# mos_motor.net
KiCad netlist of a schematic drawn in Altium Designer
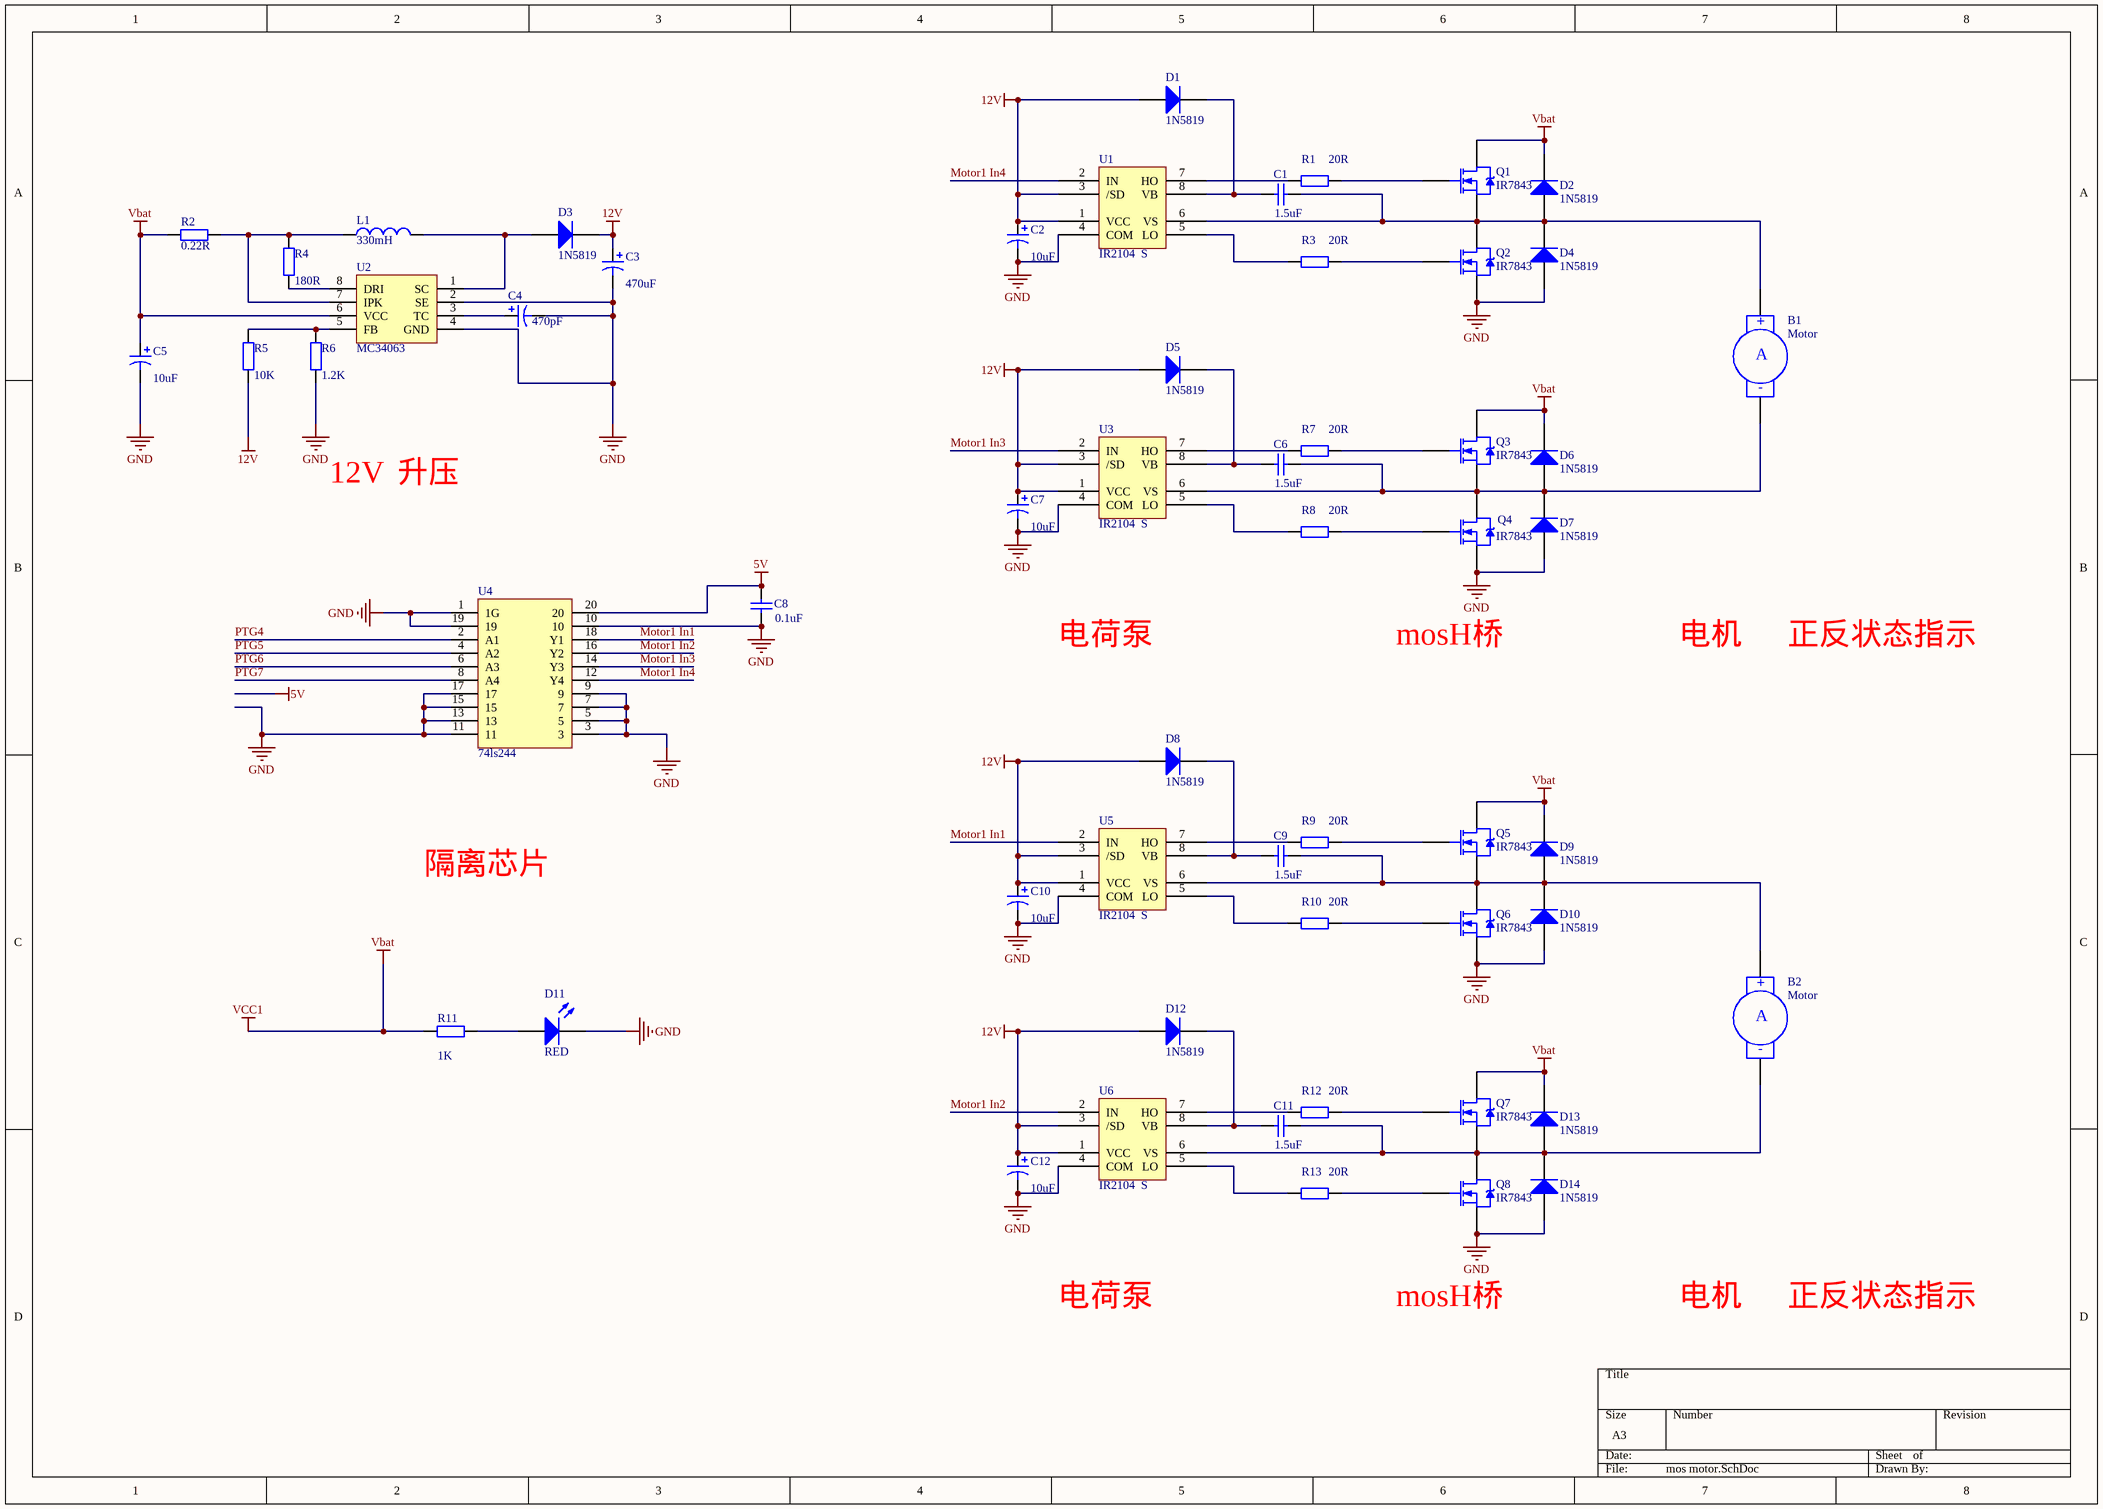
[diagram p0: mos motor.SchDoc]

(export (version "E")
  (design (tool "Eeschema 10.0.6"))
  (components
    (comp (ref "B1")
      (value "Motor")
      (footprint "KF301-2P")
      (description "Servo Motor")
      (fields (field (name "PUBLISHER") "Altium Limited"))
      (libsource (lib "Miscellaneous Devices") (part "Motor Servo"))
    )
    (comp (ref "B2")
      (value "Motor")
      (footprint "KF301-2P")
      (description "Servo Motor")
      (fields (field (name "PUBLISHER") "Altium Limited"))
      (libsource (lib "Miscellaneous Devices") (part "Motor Servo"))
    )
    (comp (ref "C1")
      (value "1.5uF")
      (footprint "0805(2012)")
      (description "Capacitor")
      (fields (field (name "Comment") "Cap") (field (name "PUBLISHER") "Altium Limited"))
      (libsource (lib "Miscellaneous Devices") (part "Cap"))
    )
    (comp (ref "C2")
      (value "10uF")
      (footprint "SOD-323(0805)")
      (description "Polarized Capacitor (Radial)")
      (fields (field (name "Comment") "Cap Pol1") (field (name "PUBLISHER") "Altium Limited"))
      (libsource (lib "Miscellaneous Devices") (part "Cap Pol1"))
    )
    (comp (ref "C3")
      (value "470uF")
      (footprint "RB5-10.5")
      (description "Polarized Capacitor (Radial)")
      (fields (field (name "Comment") "Cap Pol1") (field (name "PUBLISHER") "Altium Limited"))
      (libsource (lib "Miscellaneous Devices") (part "Cap Pol1"))
    )
    (comp (ref "C4")
      (value "470pF")
      (footprint "SOD-323(0805)")
      (description "Polarized Capacitor (Radial)")
      (fields (field (name "Comment") "Cap Pol1") (field (name "PUBLISHER") "Altium Limited"))
      (libsource (lib "Miscellaneous Devices") (part "Cap Pol1"))
    )
    (comp (ref "C5")
      (value "10uF")
      (footprint "SOD-323(0805)")
      (description "Polarized Capacitor (Radial)")
      (fields (field (name "Comment") "Cap Pol1") (field (name "PUBLISHER") "Altium Limited"))
      (libsource (lib "Miscellaneous Devices") (part "Cap Pol1"))
    )
    (comp (ref "C6")
      (value "1.5uF")
      (footprint "0805(2012)")
      (description "Capacitor")
      (fields (field (name "Comment") "Cap") (field (name "PUBLISHER") "Altium Limited"))
      (libsource (lib "Miscellaneous Devices") (part "Cap"))
    )
    (comp (ref "C7")
      (value "10uF")
      (footprint "SOD-323(0805)")
      (description "Polarized Capacitor (Radial)")
      (fields (field (name "Comment") "Cap Pol1") (field (name "PUBLISHER") "Altium Limited"))
      (libsource (lib "Miscellaneous Devices") (part "Cap Pol1"))
    )
    (comp (ref "C8")
      (value "0.1uF")
      (footprint "0805(2012)")
      (description "Capacitor")
      (fields (field (name "Comment") "Cap") (field (name "PUBLISHER") "Altium Limited"))
      (libsource (lib "Miscellaneous Devices") (part "Cap"))
    )
    (comp (ref "C9")
      (value "1.5uF")
      (footprint "0805(2012)")
      (description "Capacitor")
      (fields (field (name "Comment") "Cap") (field (name "PUBLISHER") "Altium Limited"))
      (libsource (lib "Miscellaneous Devices") (part "Cap"))
    )
    (comp (ref "C10")
      (value "10uF")
      (footprint "SOD-323(0805)")
      (description "Polarized Capacitor (Radial)")
      (fields (field (name "Comment") "Cap Pol1") (field (name "PUBLISHER") "Altium Limited"))
      (libsource (lib "Miscellaneous Devices") (part "Cap Pol1"))
    )
    (comp (ref "C11")
      (value "1.5uF")
      (footprint "0805(2012)")
      (description "Capacitor")
      (fields (field (name "Comment") "Cap") (field (name "PUBLISHER") "Altium Limited"))
      (libsource (lib "Miscellaneous Devices") (part "Cap"))
    )
    (comp (ref "C12")
      (value "10uF")
      (footprint "SOD-323(0805)")
      (description "Polarized Capacitor (Radial)")
      (fields (field (name "Comment") "Cap Pol1") (field (name "PUBLISHER") "Altium Limited"))
      (libsource (lib "Miscellaneous Devices") (part "Cap Pol1"))
    )
    (comp (ref "D1")
      (value "1N5819")
      (footprint "0805(2012)")
      (description "Silicon Epitaxial Planar Diode for Various Detector, Modulator, Demodulator")
      (fields (field (name "PUBLISHER") "Altium Limited"))
      (libsource (lib "Renesas Diode") (part "1N4148"))
    )
    (comp (ref "D2")
      (value "1N5819")
      (footprint "0805(2012)")
      (description "Silicon Epitaxial Planar Diode for Various Detector, Modulator, Demodulator")
      (fields (field (name "PUBLISHER") "Altium Limited"))
      (libsource (lib "Renesas Diode") (part "1N4148"))
    )
    (comp (ref "D3")
      (value "1N5819")
      (footprint "0805(2012)")
      (description "Silicon Epitaxial Planar Diode for Various Detector, Modulator, Demodulator")
      (fields (field (name "PUBLISHER") "Altium Limited"))
      (libsource (lib "Renesas Diode") (part "1N4148"))
    )
    (comp (ref "D4")
      (value "1N5819")
      (footprint "0805(2012)")
      (description "Silicon Epitaxial Planar Diode for Various Detector, Modulator, Demodulator")
      (fields (field (name "PUBLISHER") "Altium Limited"))
      (libsource (lib "13th_motor") (part "1N4148"))
    )
    (comp (ref "D5")
      (value "1N5819")
      (footprint "0805(2012)")
      (description "Silicon Epitaxial Planar Diode for Various Detector, Modulator, Demodulator")
      (fields (field (name "PUBLISHER") "Altium Limited"))
      (libsource (lib "Renesas Diode") (part "1N4148"))
    )
    (comp (ref "D6")
      (value "1N5819")
      (footprint "0805(2012)")
      (description "Silicon Epitaxial Planar Diode for Various Detector, Modulator, Demodulator")
      (fields (field (name "PUBLISHER") "Altium Limited"))
      (libsource (lib "Renesas Diode") (part "1N4148"))
    )
    (comp (ref "D7")
      (value "1N5819")
      (footprint "0805(2012)")
      (description "Silicon Epitaxial Planar Diode for Various Detector, Modulator, Demodulator")
      (fields (field (name "PUBLISHER") "Altium Limited"))
      (libsource (lib "Renesas Diode") (part "1N4148"))
    )
    (comp (ref "D8")
      (value "1N5819")
      (footprint "0805(2012)")
      (description "Silicon Epitaxial Planar Diode for Various Detector, Modulator, Demodulator")
      (fields (field (name "PUBLISHER") "Altium Limited"))
      (libsource (lib "Renesas Diode") (part "1N4148"))
    )
    (comp (ref "D9")
      (value "1N5819")
      (footprint "0805(2012)")
      (description "Silicon Epitaxial Planar Diode for Various Detector, Modulator, Demodulator")
      (fields (field (name "PUBLISHER") "Altium Limited"))
      (libsource (lib "Renesas Diode") (part "1N4148"))
    )
    (comp (ref "D10")
      (value "1N5819")
      (footprint "0805(2012)")
      (description "Silicon Epitaxial Planar Diode for Various Detector, Modulator, Demodulator")
      (fields (field (name "PUBLISHER") "Altium Limited"))
      (libsource (lib "Renesas Diode") (part "1N4148"))
    )
    (comp (ref "D11")
      (value "RED")
      (footprint "0805LED")
      (description "Typical RED, GREEN, YELLOW, AMBER GaAs LED")
      (fields (field (name "PUBLISHER") "Altium Limited"))
      (libsource (lib "Miscellaneous Devices") (part "LED2"))
    )
    (comp (ref "D12")
      (value "1N5819")
      (footprint "0805(2012)")
      (description "Silicon Epitaxial Planar Diode for Various Detector, Modulator, Demodulator")
      (fields (field (name "PUBLISHER") "Altium Limited"))
      (libsource (lib "Renesas Diode") (part "1N4148"))
    )
    (comp (ref "D13")
      (value "1N5819")
      (footprint "0805(2012)")
      (description "Silicon Epitaxial Planar Diode for Various Detector, Modulator, Demodulator")
      (fields (field (name "PUBLISHER") "Altium Limited"))
      (libsource (lib "Renesas Diode") (part "1N4148"))
    )
    (comp (ref "D14")
      (value "1N5819")
      (footprint "0805(2012)")
      (description "Silicon Epitaxial Planar Diode for Various Detector, Modulator, Demodulator")
      (fields (field (name "PUBLISHER") "Altium Limited"))
      (libsource (lib "Renesas Diode") (part "1N4148"))
    )
    (comp (ref "L1")
      (value "330mH")
      (footprint "电感10*12")
      (description "Inductor")
      (fields (field (name "PUBLISHER") "Altium Limited"))
      (libsource (lib "Miscellaneous Devices") (part "Inductor"))
    )
    (comp (ref "Q1")
      (value "IR7843")
      (footprint "LR7843")
      (description "N-Channel Power MOSFET")
      (fields (field (name "PUBLISHER") "Altium Limited"))
      (libsource (lib "PowerIn") (part "IR7843"))
    )
    (comp (ref "Q2")
      (value "IR7843")
      (footprint "LR7843")
      (description "N-Channel Power MOSFET")
      (fields (field (name "PUBLISHER") "Altium Limited"))
      (libsource (lib "PowerIn") (part "IR7843"))
    )
    (comp (ref "Q3")
      (value "IR7843")
      (footprint "LR7843")
      (description "N-Channel Power MOSFET")
      (fields (field (name "PUBLISHER") "Altium Limited"))
      (libsource (lib "PowerIn") (part "IR7843"))
    )
    (comp (ref "Q4")
      (value "IR7843")
      (footprint "LR7843")
      (description "N-Channel Power MOSFET")
      (fields (field (name "PUBLISHER") "Altium Limited"))
      (libsource (lib "PowerIn") (part "IR7843"))
    )
    (comp (ref "Q5")
      (value "IR7843")
      (footprint "LR7843")
      (description "N-Channel Power MOSFET")
      (fields (field (name "PUBLISHER") "Altium Limited"))
      (libsource (lib "PowerIn") (part "IR7843"))
    )
    (comp (ref "Q6")
      (value "IR7843")
      (footprint "LR7843")
      (description "N-Channel Power MOSFET")
      (fields (field (name "PUBLISHER") "Altium Limited"))
      (libsource (lib "PowerIn") (part "IR7843"))
    )
    (comp (ref "Q7")
      (value "IR7843")
      (footprint "LR7843")
      (description "N-Channel Power MOSFET")
      (fields (field (name "PUBLISHER") "Altium Limited"))
      (libsource (lib "PowerIn") (part "IR7843"))
    )
    (comp (ref "Q8")
      (value "IR7843")
      (footprint "LR7843")
      (description "N-Channel Power MOSFET")
      (fields (field (name "PUBLISHER") "Altium Limited"))
      (libsource (lib "PowerIn") (part "IR7843"))
    )
    (comp (ref "R1")
      (value "20R")
      (footprint "0805(2012)")
      (description "Resistor")
      (fields (field (name "Comment") "Res2") (field (name "PUBLISHER") "Altium Limited"))
      (libsource (lib "altium-import") (part "root_0_Res2_"))
    )
    (comp (ref "R2")
      (value "0.22R")
      (footprint "1206(3216)")
      (description "Resistor")
      (fields (field (name "Comment") "Res2") (field (name "PUBLISHER") "Altium Limited"))
      (libsource (lib "altium-import") (part "root_2_Res2_"))
    )
    (comp (ref "R3")
      (value "20R")
      (footprint "0805(2012)")
      (description "Resistor")
      (fields (field (name "Comment") "Res2") (field (name "PUBLISHER") "Altium Limited"))
      (libsource (lib "altium-import") (part "root_0_Res2_"))
    )
    (comp (ref "R4")
      (value "180R")
      (footprint "0805(2012)")
      (description "Resistor")
      (fields (field (name "Comment") "Res2") (field (name "PUBLISHER") "Altium Limited"))
      (libsource (lib "altium-import") (part "root_1_Res2_"))
    )
    (comp (ref "R5")
      (value "10K")
      (footprint "0805(2012)")
      (description "Resistor")
      (fields (field (name "Comment") "Res2") (field (name "PUBLISHER") "Altium Limited"))
      (libsource (lib "altium-import") (part "root_1_Res2_"))
    )
    (comp (ref "R6")
      (value "1.2K")
      (footprint "0805(2012)")
      (description "Resistor")
      (fields (field (name "Comment") "Res2") (field (name "PUBLISHER") "Altium Limited"))
      (libsource (lib "altium-import") (part "root_1_Res2_"))
    )
    (comp (ref "R7")
      (value "20R")
      (footprint "0805(2012)")
      (description "Resistor")
      (fields (field (name "Comment") "Res2") (field (name "PUBLISHER") "Altium Limited"))
      (libsource (lib "altium-import") (part "root_0_Res2_"))
    )
    (comp (ref "R8")
      (value "20R")
      (footprint "0805(2012)")
      (description "Resistor")
      (fields (field (name "Comment") "Res2") (field (name "PUBLISHER") "Altium Limited"))
      (libsource (lib "altium-import") (part "root_0_Res2_"))
    )
    (comp (ref "R9")
      (value "20R")
      (footprint "0805(2012)")
      (description "Resistor")
      (fields (field (name "Comment") "Res2") (field (name "PUBLISHER") "Altium Limited"))
      (libsource (lib "altium-import") (part "root_0_Res2_"))
    )
    (comp (ref "R10")
      (value "20R")
      (footprint "0805(2012)")
      (description "Resistor")
      (fields (field (name "Comment") "Res2") (field (name "PUBLISHER") "Altium Limited"))
      (libsource (lib "altium-import") (part "root_0_Res2_"))
    )
    (comp (ref "R11")
      (value "1K")
      (footprint "0805(2012)")
      (description "Resistor")
      (fields (field (name "Comment") "Res2") (field (name "PUBLISHER") "Altium Limited"))
      (libsource (lib "Miscellaneous Devices") (part "Res2"))
    )
    (comp (ref "R12")
      (value "20R")
      (footprint "0805(2012)")
      (description "Resistor")
      (fields (field (name "Comment") "Res2") (field (name "PUBLISHER") "Altium Limited"))
      (libsource (lib "altium-import") (part "root_0_Res2_"))
    )
    (comp (ref "R13")
      (value "20R")
      (footprint "0805(2012)")
      (description "Resistor")
      (fields (field (name "Comment") "Res2") (field (name "PUBLISHER") "Altium Limited"))
      (libsource (lib "altium-import") (part "root_0_Res2_"))
    )
    (comp (ref "U1") (value "IR2104  S") (footprint "IR2104S") (libsource (lib "IR2104S") (part "IR2104  S")))
    (comp (ref "U2") (value "MC34063") (footprint "MC34063") (libsource (lib "MC34063") (part "Component_1")))
    (comp (ref "U3") (value "IR2104  S") (footprint "IR2104S") (libsource (lib "IR2104S") (part "IR2104  S")))
    (comp (ref "U4") (value "74ls244") (footprint "74ls244Da") (libsource (lib "MOS motor") (part "74ls244")))
    (comp (ref "U5") (value "IR2104  S") (footprint "IR2104S") (libsource (lib "IR2104S") (part "IR2104  S")))
    (comp (ref "U6") (value "IR2104  S") (footprint "IR2104S") (libsource (lib "IR2104S") (part "IR2104  S")))
  )
  (nets
    (net (code "1") (name "/Motor1 In1") (class "Default")
      (node (ref "U4") (pin "18") (pinfunction "Y1_18") (pintype "passive"))
      (node (ref "U5") (pin "2") (pinfunction "IN_2") (pintype "passive"))
    )
    (net (code "2") (name "/Motor1 In2") (class "Default")
      (node (ref "U4") (pin "16") (pinfunction "Y2_16") (pintype "passive"))
      (node (ref "U6") (pin "2") (pinfunction "IN_2") (pintype "passive"))
    )
    (net (code "3") (name "/Motor1 In3") (class "Default")
      (node (ref "U3") (pin "2") (pinfunction "IN_2") (pintype "passive"))
      (node (ref "U4") (pin "14") (pinfunction "Y3_14") (pintype "passive"))
    )
    (net (code "4") (name "/Motor1 In4") (class "Default")
      (node (ref "U1") (pin "2") (pinfunction "IN_2") (pintype "passive"))
      (node (ref "U4") (pin "12") (pinfunction "Y4_12") (pintype "passive"))
    )
    (net (code "5") (name "/PTG4") (class "Default")
      (node (ref "U4") (pin "2") (pinfunction "A1_2") (pintype "passive"))
    )
    (net (code "6") (name "/PTG5") (class "Default")
      (node (ref "U4") (pin "4") (pinfunction "A2_4") (pintype "passive"))
    )
    (net (code "7") (name "/PTG6") (class "Default")
      (node (ref "U4") (pin "6") (pinfunction "A3_6") (pintype "passive"))
    )
    (net (code "8") (name "/PTG7") (class "Default")
      (node (ref "U4") (pin "8") (pinfunction "A4_8") (pintype "passive"))
    )
    (net (code "9") (name "5V") (class "Default")
      (node (ref "C8") (pin "2") (pinfunction "2_2") (pintype "passive"))
      (node (ref "U4") (pin "20") (pinfunction "20_20") (pintype "passive"))
    )
    (net (code "10") (name "12V") (class "Default")
      (node (ref "C10") (pin "1") (pinfunction "1_1") (pintype "passive"))
      (node (ref "C12") (pin "1") (pinfunction "1_1") (pintype "passive"))
      (node (ref "C2") (pin "1") (pinfunction "1_1") (pintype "passive"))
      (node (ref "C3") (pin "1") (pinfunction "1_1") (pintype "passive"))
      (node (ref "C7") (pin "1") (pinfunction "1_1") (pintype "passive"))
      (node (ref "D1") (pin "2") (pinfunction "A_2") (pintype "passive"))
      (node (ref "D12") (pin "2") (pinfunction "A_2") (pintype "passive"))
      (node (ref "D3") (pin "1") (pinfunction "K_1") (pintype "passive"))
      (node (ref "D5") (pin "2") (pinfunction "A_2") (pintype "passive"))
      (node (ref "D8") (pin "2") (pinfunction "A_2") (pintype "passive"))
      (node (ref "R5") (pin "1") (pinfunction "1_1") (pintype "passive"))
      (node (ref "U1") (pin "1") (pinfunction "VCC_1") (pintype "passive"))
      (node (ref "U1") (pin "3") (pinfunction "/SD_3") (pintype "passive"))
      (node (ref "U3") (pin "1") (pinfunction "VCC_1") (pintype "passive"))
      (node (ref "U3") (pin "3") (pinfunction "/SD_3") (pintype "passive"))
      (node (ref "U5") (pin "1") (pinfunction "VCC_1") (pintype "passive"))
      (node (ref "U5") (pin "3") (pinfunction "/SD_3") (pintype "passive"))
      (node (ref "U6") (pin "1") (pinfunction "VCC_1") (pintype "passive"))
      (node (ref "U6") (pin "3") (pinfunction "/SD_3") (pintype "passive"))
    )
    (net (code "11") (name "GND") (class "Default")
      (node (ref "C10") (pin "2") (pinfunction "2_2") (pintype "passive"))
      (node (ref "C12") (pin "2") (pinfunction "2_2") (pintype "passive"))
      (node (ref "C2") (pin "2") (pinfunction "2_2") (pintype "passive"))
      (node (ref "C3") (pin "2") (pinfunction "2_2") (pintype "passive"))
      (node (ref "C4") (pin "2") (pinfunction "2_2") (pintype "passive"))
      (node (ref "C5") (pin "2") (pinfunction "2_2") (pintype "passive"))
      (node (ref "C7") (pin "2") (pinfunction "2_2") (pintype "passive"))
      (node (ref "C8") (pin "1") (pinfunction "1_1") (pintype "passive"))
      (node (ref "D10") (pin "2") (pinfunction "A_2") (pintype "passive"))
      (node (ref "D11") (pin "2") (pinfunction "K_2") (pintype "passive"))
      (node (ref "D14") (pin "2") (pinfunction "A_2") (pintype "passive"))
      (node (ref "D4") (pin "2") (pinfunction "A_2") (pintype "passive"))
      (node (ref "D7") (pin "2") (pinfunction "A_2") (pintype "passive"))
      (node (ref "Q2") (pin "3") (pinfunction "S_3") (pintype "passive"))
      (node (ref "Q4") (pin "3") (pinfunction "S_3") (pintype "passive"))
      (node (ref "Q6") (pin "3") (pinfunction "S_3") (pintype "passive"))
      (node (ref "Q8") (pin "3") (pinfunction "S_3") (pintype "passive"))
      (node (ref "R6") (pin "1") (pinfunction "1_1") (pintype "passive"))
      (node (ref "U1") (pin "4") (pinfunction "COM_4") (pintype "passive"))
      (node (ref "U2") (pin "2") (pinfunction "SE_2") (pintype "passive"))
      (node (ref "U2") (pin "4") (pinfunction "GND_4") (pintype "passive"))
      (node (ref "U3") (pin "4") (pinfunction "COM_4") (pintype "passive"))
      (node (ref "U4") (pin "1") (pinfunction "1G_1") (pintype "passive"))
      (node (ref "U4") (pin "10") (pinfunction "10_10") (pintype "passive"))
      (node (ref "U4") (pin "11") (pinfunction "11_11") (pintype "passive"))
      (node (ref "U4") (pin "13") (pinfunction "13_13") (pintype "passive"))
      (node (ref "U4") (pin "15") (pinfunction "15_15") (pintype "passive"))
      (node (ref "U4") (pin "17") (pinfunction "17_17") (pintype "passive"))
      (node (ref "U4") (pin "19") (pinfunction "19_19") (pintype "passive"))
      (node (ref "U4") (pin "3") (pinfunction "3_3") (pintype "passive"))
      (node (ref "U4") (pin "5") (pinfunction "5_5") (pintype "passive"))
      (node (ref "U4") (pin "7") (pinfunction "7_7") (pintype "passive"))
      (node (ref "U4") (pin "9") (pinfunction "9_9") (pintype "passive"))
      (node (ref "U5") (pin "4") (pinfunction "COM_4") (pintype "passive"))
      (node (ref "U6") (pin "4") (pinfunction "COM_4") (pintype "passive"))
    )
    (net (code "12") (name "Net-(B1-+)") (class "Default")
      (node (ref "B1") (pin "1") (pinfunction "+_1") (pintype "passive"))
      (node (ref "C1") (pin "2") (pinfunction "2_2") (pintype "passive"))
      (node (ref "D2") (pin "2") (pinfunction "A_2") (pintype "passive"))
      (node (ref "D4") (pin "1") (pinfunction "K_1") (pintype "passive"))
      (node (ref "Q1") (pin "3") (pinfunction "S_3") (pintype "passive"))
      (node (ref "Q2") (pin "2") (pinfunction "D_2") (pintype "passive"))
      (node (ref "U1") (pin "6") (pinfunction "VS_6") (pintype "passive"))
    )
    (net (code "13") (name "Net-(B1--)") (class "Default")
      (node (ref "B1") (pin "2") (pinfunction "-_2") (pintype "passive"))
      (node (ref "C6") (pin "2") (pinfunction "2_2") (pintype "passive"))
      (node (ref "D6") (pin "2") (pinfunction "A_2") (pintype "passive"))
      (node (ref "D7") (pin "1") (pinfunction "K_1") (pintype "passive"))
      (node (ref "Q3") (pin "3") (pinfunction "S_3") (pintype "passive"))
      (node (ref "Q4") (pin "2") (pinfunction "D_2") (pintype "passive"))
      (node (ref "U3") (pin "6") (pinfunction "VS_6") (pintype "passive"))
    )
    (net (code "14") (name "Net-(B2-+)") (class "Default")
      (node (ref "B2") (pin "1") (pinfunction "+_1") (pintype "passive"))
      (node (ref "C9") (pin "2") (pinfunction "2_2") (pintype "passive"))
      (node (ref "D10") (pin "1") (pinfunction "K_1") (pintype "passive"))
      (node (ref "D9") (pin "2") (pinfunction "A_2") (pintype "passive"))
      (node (ref "Q5") (pin "3") (pinfunction "S_3") (pintype "passive"))
      (node (ref "Q6") (pin "2") (pinfunction "D_2") (pintype "passive"))
      (node (ref "U5") (pin "6") (pinfunction "VS_6") (pintype "passive"))
    )
    (net (code "15") (name "Net-(B2--)") (class "Default")
      (node (ref "B2") (pin "2") (pinfunction "-_2") (pintype "passive"))
      (node (ref "C11") (pin "2") (pinfunction "2_2") (pintype "passive"))
      (node (ref "D13") (pin "2") (pinfunction "A_2") (pintype "passive"))
      (node (ref "D14") (pin "1") (pinfunction "K_1") (pintype "passive"))
      (node (ref "Q7") (pin "3") (pinfunction "S_3") (pintype "passive"))
      (node (ref "Q8") (pin "2") (pinfunction "D_2") (pintype "passive"))
      (node (ref "U6") (pin "6") (pinfunction "VS_6") (pintype "passive"))
    )
    (net (code "16") (name "Net-(D1-K)") (class "Default")
      (node (ref "C1") (pin "1") (pinfunction "1_1") (pintype "passive"))
      (node (ref "D1") (pin "1") (pinfunction "K_1") (pintype "passive"))
      (node (ref "U1") (pin "8") (pinfunction "VB_8") (pintype "passive"))
    )
    (net (code "17") (name "Net-(D3-A)") (class "Default")
      (node (ref "D3") (pin "2") (pinfunction "A_2") (pintype "passive"))
      (node (ref "L1") (pin "2") (pinfunction "2_2") (pintype "passive"))
      (node (ref "U2") (pin "1") (pinfunction "SC_1") (pintype "passive"))
    )
    (net (code "18") (name "Net-(D5-K)") (class "Default")
      (node (ref "C6") (pin "1") (pinfunction "1_1") (pintype "passive"))
      (node (ref "D5") (pin "1") (pinfunction "K_1") (pintype "passive"))
      (node (ref "U3") (pin "8") (pinfunction "VB_8") (pintype "passive"))
    )
    (net (code "19") (name "Net-(D8-K)") (class "Default")
      (node (ref "C9") (pin "1") (pinfunction "1_1") (pintype "passive"))
      (node (ref "D8") (pin "1") (pinfunction "K_1") (pintype "passive"))
      (node (ref "U5") (pin "8") (pinfunction "VB_8") (pintype "passive"))
    )
    (net (code "20") (name "Net-(D11-A)") (class "Default")
      (node (ref "D11") (pin "1") (pinfunction "A_1") (pintype "passive"))
      (node (ref "R11") (pin "2") (pinfunction "2_2") (pintype "passive"))
    )
    (net (code "21") (name "Net-(D12-K)") (class "Default")
      (node (ref "C11") (pin "1") (pinfunction "1_1") (pintype "passive"))
      (node (ref "D12") (pin "1") (pinfunction "K_1") (pintype "passive"))
      (node (ref "U6") (pin "8") (pinfunction "VB_8") (pintype "passive"))
    )
    (net (code "22") (name "Net-(Q1-G)") (class "Default")
      (node (ref "Q1") (pin "1") (pinfunction "G_1") (pintype "passive"))
      (node (ref "R1") (pin "2") (pinfunction "2_2") (pintype "passive"))
    )
    (net (code "23") (name "Net-(Q2-G)") (class "Default")
      (node (ref "Q2") (pin "1") (pinfunction "G_1") (pintype "passive"))
      (node (ref "R3") (pin "2") (pinfunction "2_2") (pintype "passive"))
    )
    (net (code "24") (name "Net-(Q3-G)") (class "Default")
      (node (ref "Q3") (pin "1") (pinfunction "G_1") (pintype "passive"))
      (node (ref "R7") (pin "2") (pinfunction "2_2") (pintype "passive"))
    )
    (net (code "25") (name "Net-(Q4-G)") (class "Default")
      (node (ref "Q4") (pin "1") (pinfunction "G_1") (pintype "passive"))
      (node (ref "R8") (pin "2") (pinfunction "2_2") (pintype "passive"))
    )
    (net (code "26") (name "Net-(Q5-G)") (class "Default")
      (node (ref "Q5") (pin "1") (pinfunction "G_1") (pintype "passive"))
      (node (ref "R9") (pin "2") (pinfunction "2_2") (pintype "passive"))
    )
    (net (code "27") (name "Net-(Q6-G)") (class "Default")
      (node (ref "Q6") (pin "1") (pinfunction "G_1") (pintype "passive"))
      (node (ref "R10") (pin "2") (pinfunction "2_2") (pintype "passive"))
    )
    (net (code "28") (name "Net-(Q7-G)") (class "Default")
      (node (ref "Q7") (pin "1") (pinfunction "G_1") (pintype "passive"))
      (node (ref "R12") (pin "2") (pinfunction "2_2") (pintype "passive"))
    )
    (net (code "29") (name "Net-(Q8-G)") (class "Default")
      (node (ref "Q8") (pin "1") (pinfunction "G_1") (pintype "passive"))
      (node (ref "R13") (pin "2") (pinfunction "2_2") (pintype "passive"))
    )
    (net (code "30") (name "Net-(U1-HO)") (class "Default")
      (node (ref "R1") (pin "1") (pinfunction "1_1") (pintype "passive"))
      (node (ref "U1") (pin "7") (pinfunction "HO_7") (pintype "passive"))
    )
    (net (code "31") (name "Net-(U1-LO)") (class "Default")
      (node (ref "R3") (pin "1") (pinfunction "1_1") (pintype "passive"))
      (node (ref "U1") (pin "5") (pinfunction "LO_5") (pintype "passive"))
    )
    (net (code "32") (name "Net-(U2-DRI)") (class "Default")
      (node (ref "R4") (pin "1") (pinfunction "1_1") (pintype "passive"))
      (node (ref "U2") (pin "8") (pinfunction "DRI_8") (pintype "passive"))
    )
    (net (code "33") (name "Net-(U2-FB)") (class "Default")
      (node (ref "R5") (pin "2") (pinfunction "2_2") (pintype "passive"))
      (node (ref "R6") (pin "2") (pinfunction "2_2") (pintype "passive"))
      (node (ref "U2") (pin "5") (pinfunction "FB_5") (pintype "passive"))
    )
    (net (code "34") (name "Net-(U2-IPK)") (class "Default")
      (node (ref "L1") (pin "1") (pinfunction "1_1") (pintype "passive"))
      (node (ref "R2") (pin "1") (pinfunction "1_1") (pintype "passive"))
      (node (ref "R4") (pin "2") (pinfunction "2_2") (pintype "passive"))
      (node (ref "U2") (pin "7") (pinfunction "IPK_7") (pintype "passive"))
    )
    (net (code "35") (name "Net-(U2-TC)") (class "Default")
      (node (ref "C4") (pin "1") (pinfunction "1_1") (pintype "passive"))
      (node (ref "U2") (pin "3") (pinfunction "TC_3") (pintype "passive"))
    )
    (net (code "36") (name "Net-(U3-HO)") (class "Default")
      (node (ref "R7") (pin "1") (pinfunction "1_1") (pintype "passive"))
      (node (ref "U3") (pin "7") (pinfunction "HO_7") (pintype "passive"))
    )
    (net (code "37") (name "Net-(U3-LO)") (class "Default")
      (node (ref "R8") (pin "1") (pinfunction "1_1") (pintype "passive"))
      (node (ref "U3") (pin "5") (pinfunction "LO_5") (pintype "passive"))
    )
    (net (code "38") (name "Net-(U5-HO)") (class "Default")
      (node (ref "R9") (pin "1") (pinfunction "1_1") (pintype "passive"))
      (node (ref "U5") (pin "7") (pinfunction "HO_7") (pintype "passive"))
    )
    (net (code "39") (name "Net-(U5-LO)") (class "Default")
      (node (ref "R10") (pin "1") (pinfunction "1_1") (pintype "passive"))
      (node (ref "U5") (pin "5") (pinfunction "LO_5") (pintype "passive"))
    )
    (net (code "40") (name "Net-(U6-HO)") (class "Default")
      (node (ref "R12") (pin "1") (pinfunction "1_1") (pintype "passive"))
      (node (ref "U6") (pin "7") (pinfunction "HO_7") (pintype "passive"))
    )
    (net (code "41") (name "Net-(U6-LO)") (class "Default")
      (node (ref "R13") (pin "1") (pinfunction "1_1") (pintype "passive"))
      (node (ref "U6") (pin "5") (pinfunction "LO_5") (pintype "passive"))
    )
    (net (code "42") (name "VCC1") (class "Default")
      (node (ref "C5") (pin "1") (pinfunction "1_1") (pintype "passive"))
      (node (ref "D13") (pin "1") (pinfunction "K_1") (pintype "passive"))
      (node (ref "D2") (pin "1") (pinfunction "K_1") (pintype "passive"))
      (node (ref "D6") (pin "1") (pinfunction "K_1") (pintype "passive"))
      (node (ref "D9") (pin "1") (pinfunction "K_1") (pintype "passive"))
      (node (ref "Q1") (pin "2") (pinfunction "D_2") (pintype "passive"))
      (node (ref "Q3") (pin "2") (pinfunction "D_2") (pintype "passive"))
      (node (ref "Q5") (pin "2") (pinfunction "D_2") (pintype "passive"))
      (node (ref "Q7") (pin "2") (pinfunction "D_2") (pintype "passive"))
      (node (ref "R11") (pin "1") (pinfunction "1_1") (pintype "passive"))
      (node (ref "R2") (pin "2") (pinfunction "2_2") (pintype "passive"))
      (node (ref "U2") (pin "6") (pinfunction "VCC_6") (pintype "passive"))
    )
  )
)
